# 12V_Buck.net
KiCad netlist of a schematic drawn in Altium Designer
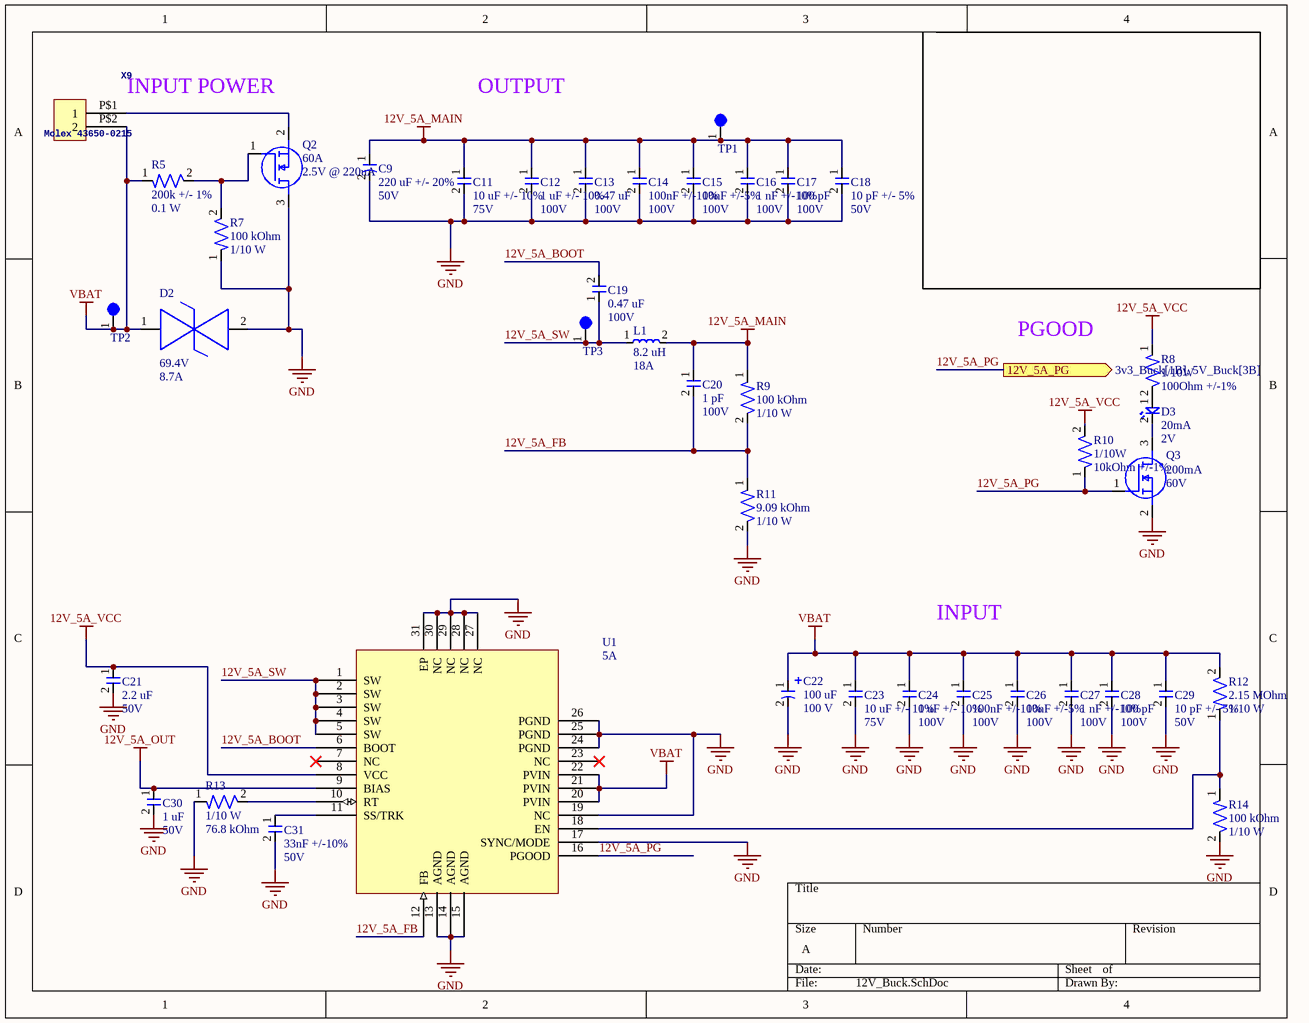
[diagram p0: 12V_Buck.SchDoc]

(export (version "E")
  (design (tool "Eeschema 10.0.6"))
  (components
    (comp (ref "C9")
      (value "50TZV220M10X10.5")
      (footprint "ELEC-220U-0003")
      (description "220 µF 50 V Aluminum Electrolytic Capacitors Radial, Can - SMD 2000 Hrs @ 105°C")
      (fields (field (name "CAPACITANCE") "220 uF +/- 20%") (field (name "VOLTAGE RATING") "50V"))
      (libsource (lib "MasterLib") (part "ELEC-220U-0003"))
    )
    (comp (ref "C11")
      (value "C3225X7R1N106K250AC")
      (footprint "CAP-1210")
      (description "10 µF ±10% 75V Ceramic Capacitor X7R 1210 (3225 Metric)")
      (fields (field (name "CAPACITANCE") "10 uF +/- 10%") (field (name "VOLTAGE RATING") "75V"))
      (libsource (lib "MasterLib") (part "CAP-10U-0004"))
    )
    (comp (ref "C12")
      (value "CL31B105KCHNNNE")
      (footprint "CAP-1206 - duplicate")
      (description "1 µF ±10% 100V Ceramic Capacitor X7R 1206 (3216 Metric)")
      (fields (field (name "CAPACITANCE") "1 uF +/- 10%") (field (name "VOLTAGE") "100V"))
      (libsource (lib "MasterLib") (part "CAP-1U-0001"))
    )
    (comp (ref "C13")
      (value "KAM21KR72A474KL")
      (footprint "CAP-0805")
      (description "0.47 µF ±10% 100V Ceramic Capacitor X7R 0805 (2012 Metric)")
      (fields
        (field (name "TOLERANCE") "+/- 10%")
        (field (name "CAPACITANCE") "0.47 uF")
        (field (name "VOLTAGE") "100V")
      )
      (libsource (lib "MasterLib") (part "CAP-0.47U-0001"))
    )
    (comp (ref "C14")
      (value "CC0603KRX7R0BB104")
      (footprint "CAP-0603")
      (description "CAP CER 0.1UF 100V X7R 0603")
      (fields
        (field (name "MANUFACTURER") "YAGEO")
        (field (name "CAPACITANCE") "100nF +/-10%")
        (field (name "VOLTAGE RATING") "100V")
      )
      (libsource (lib "MasterLib") (part "CAP-100N-0001"))
    )
    (comp (ref "C15")
      (value "C1608C0G2A103J080AC")
      (footprint "CAP-0603")
      (description "CAP CER 10000PF 100V C0G 0603")
      (fields
        (field (name "MANUFACTURER") "TDK Corporation")
        (field (name "CAPACITANCE") "10nF +/-5%")
        (field (name "VOLTAGE RATING") "100V")
      )
      (libsource (lib "MasterLib") (part "CAP-10N-0002"))
    )
    (comp (ref "C16")
      (value "C0603Y102K1RAC7867")
      (footprint "CAP-0603")
      (description "1000 pF ±10% 100V Ceramic Capacitor X7R 0603 (1608 Metric)")
      (fields (field (name "CAPACITANCE") "1 nF +/-10%") (field (name "VOLTAGE") "100V"))
      (libsource (lib "MasterLib") (part "CAP-1N-0001"))
    )
    (comp (ref "C17")
      (value "0603N101J101CT")
      (footprint "CAP-0603")
      (description "100 pF ±5% 100V Ceramic Capacitor C0G, NP0 0603 (1608 Metric)")
      (fields
        (field (name "TOLERANCE") "+/-5%")
        (field (name "CAPACITANCE") "100 pF")
        (field (name "VOLTAGE") "100V")
      )
      (libsource (lib "MasterLib") (part "CAP-100P-0002"))
    )
    (comp (ref "C18")
      (value "0603N100J500CT")
      (footprint "CAP-0603")
      (description "10 pF ±5% 50V Ceramic Capacitor C0G, NP0 0603 (1608 Metric)")
      (fields
        (field (name "MANUFACTURER") "Walshin Technology Corporation")
        (field (name "CAPACITANCE") "10 pF +/- 5%")
        (field (name "VOLTAGE RATING") "50V")
      )
      (libsource (lib "MasterLib") (part "CAP-10P-0001"))
    )
    (comp (ref "C19")
      (value "KAM21KR72A474KL")
      (footprint "CAP-0805")
      (description "0.47 µF ±10% 100V Ceramic Capacitor X7R 0805 (2012 Metric)")
      (fields
        (field (name "TOLERANCE") "+/- 10%")
        (field (name "CAPACITANCE") "0.47 uF")
        (field (name "VOLTAGE") "100V")
      )
      (libsource (lib "MasterLib") (part "CAP-0.47U-0001"))
    )
    (comp (ref "C20")
      (value "885012006087")
      (footprint "CAP-0603")
      (description "1 pF ±0.25pF 100V Ceramic Capacitor C0G, NP0 0603 (1608 Metric)")
      (fields
        (field (name "TOLERANCE") "+/- 0.25 pF")
        (field (name "CAPACITANCE") "1 pF")
        (field (name "VOLTAGE") "100V")
      )
      (libsource (lib "MasterLib") (part "CAP-1P-0001"))
    )
    (comp (ref "C21")
      (value "UMK107BBJ225KA-T")
      (footprint "CAP-0603")
      (description "2.2 µF ±10% 50V Ceramic Capacitor X5R 0603 (1608 Metric)")
      (fields (field (name "CAPACITANCE") "2.2 uF") (field (name "OLTAGE") "50V"))
      (libsource (lib "MasterLib") (part "CAP-2.2U-0001"))
    )
    (comp (ref "C22")
      (value "100SEV100M12.5X16")
      (footprint "ELEC-100U-0001")
      (description "100 µF 100 V Aluminum Electrolytic Capacitors Radial, Can - SMD 2000 Hrs @ 85°C")
      (fields
        (field (name "MANUFACTURER") "Rubycon")
        (field (name "TOLERANCE") "+/- 20%")
        (field (name "CAPACITANCE") "100 uF")
        (field (name "VOLTAGE") "100 V")
      )
      (libsource (lib "MasterLib") (part "ELEC-100U-0001"))
    )
    (comp (ref "C23")
      (value "C3225X7R1N106K250AC")
      (footprint "CAP-1210")
      (description "10 µF ±10% 75V Ceramic Capacitor X7R 1210 (3225 Metric)")
      (fields (field (name "CAPACITANCE") "10 uF +/- 10%") (field (name "VOLTAGE RATING") "75V"))
      (libsource (lib "MasterLib") (part "CAP-10U-0004"))
    )
    (comp (ref "C24")
      (value "CL31B105KCHNNNE")
      (footprint "CAP-1206 - duplicate")
      (description "1 µF ±10% 100V Ceramic Capacitor X7R 1206 (3216 Metric)")
      (fields (field (name "CAPACITANCE") "1 uF +/- 10%") (field (name "VOLTAGE") "100V"))
      (libsource (lib "MasterLib") (part "CAP-1U-0001"))
    )
    (comp (ref "C25")
      (value "CC0603KRX7R0BB104")
      (footprint "CAP-0603")
      (description "CAP CER 0.1UF 100V X7R 0603")
      (fields
        (field (name "MANUFACTURER") "YAGEO")
        (field (name "CAPACITANCE") "100nF +/-10%")
        (field (name "VOLTAGE RATING") "100V")
      )
      (libsource (lib "MasterLib") (part "CAP-100N-0001"))
    )
    (comp (ref "C26")
      (value "C1608C0G2A103J080AC")
      (footprint "CAP-0603")
      (description "CAP CER 10000PF 100V C0G 0603")
      (fields
        (field (name "MANUFACTURER") "TDK Corporation")
        (field (name "CAPACITANCE") "10nF +/-5%")
        (field (name "VOLTAGE RATING") "100V")
      )
      (libsource (lib "MasterLib") (part "CAP-10N-0002"))
    )
    (comp (ref "C27")
      (value "C0603Y102K1RAC7867")
      (footprint "CAP-0603")
      (description "1000 pF ±10% 100V Ceramic Capacitor X7R 0603 (1608 Metric)")
      (fields (field (name "CAPACITANCE") "1 nF +/-10%") (field (name "VOLTAGE") "100V"))
      (libsource (lib "MasterLib") (part "CAP-1N-0001"))
    )
    (comp (ref "C28")
      (value "0603N101J101CT")
      (footprint "CAP-0603")
      (description "100 pF ±5% 100V Ceramic Capacitor C0G, NP0 0603 (1608 Metric)")
      (fields
        (field (name "TOLERANCE") "+/-5%")
        (field (name "CAPACITANCE") "100 pF")
        (field (name "VOLTAGE") "100V")
      )
      (libsource (lib "MasterLib") (part "CAP-100P-0002"))
    )
    (comp (ref "C29")
      (value "0603N100J500CT")
      (footprint "CAP-0603")
      (description "10 pF ±5% 50V Ceramic Capacitor C0G, NP0 0603 (1608 Metric)")
      (fields
        (field (name "MANUFACTURER") "Walshin Technology Corporation")
        (field (name "CAPACITANCE") "10 pF +/- 5%")
        (field (name "VOLTAGE RATING") "50V")
      )
      (libsource (lib "MasterLib") (part "CAP-10P-0001"))
    )
    (comp (ref "C30")
      (value "UMK107AB7105KA-T")
      (footprint "CAP-0603")
      (description "1 µF ±10% 50V Ceramic Capacitor X7R 0603 (1608 Metric)")
      (fields (field (name "CAPACITANCE") "1 uF") (field (name "VOLTAGE") "50V"))
      (libsource (lib "MasterLib") (part "CAP-1U-0002"))
    )
    (comp (ref "C31")
      (value "CC0603KRX7R9BB333")
      (footprint "CAP-0603")
      (description "0.033 µF ±10% 50V Ceramic Capacitor X7R 0603 (1608 Metric)")
      (fields
        (field (name "MANUFACTURER") "YAGEO")
        (field (name "CAPACITANCE") "33nF +/-10%")
        (field (name "VOLTAGE RATING") "50V")
      )
      (libsource (lib "MasterLib") (part "CAP-33N-0001"))
    )
    (comp (ref "D2")
      (value "SMBJE43CAH")
      (footprint "DO-214AA (SMBJ)")
      (description "69.4V Clamp 8.7A Ipp Tvs Diode Surface Mount DO-214AA (SMBJ)")
      (fields (field (name "VCLAMP") "69.4V") (field (name "PEAK PULSER CURRENT") "8.7A"))
      (libsource (lib "MasterLib") (part "DIO-69.4V-0001"))
    )
    (comp (ref "D3")
      (value "150060AS75000")
      (footprint "LED-0603")
      (description "CAP CER 0.1UF 100V X7R 0603")
      (fields
        (field (name "MANUFACTURER") "Wurth Electronik")
        (field (name "CURRENT RATING") "20mA")
        (field (name "VF") "2V")
      )
      (libsource (lib "MasterLib") (part "LED_Amber_0001"))
    )
    (comp (ref "L1")
      (value "IHLP6767GZER8R2M01")
      (footprint "PWRIND-8.2U-0002")
      (description "8.2 µH Shielded Molded Inductor 18 A 10.66mOhm Max Nonstandard")
      (fields
        (field (name "TOLERANCE") "+/-20%")
        (field (name "INDUCTANCE") "8.2 uH")
        (field (name "DCI") "18A")
      )
      (libsource (lib "MasterLib") (part "PWRIND-8.2U-0002"))
    )
    (comp (ref "Q2")
      (value "TPH7R006PL,L1Q")
      (footprint "NMOS-8PowerVDFN")
      (description "N-Channel 60 V 60A (Tc) 81W (Tc) Surface Mount 8-SOP Advance (5x5)")
      (fields (field (name "DRAIN CURRENT") "60A") (field (name "VGS") "2.5V @ 220uA"))
      (libsource (lib "MasterLib") (part "NMOS-60A-0001"))
    )
    (comp (ref "Q3")
      (value "T2N7002AK,LM")
      (footprint "NMOS-SOT23-3")
      (description "MOSFET N-CH 60V 200MA SOT23")
      (fields
        (field (name "MANUFACTURER") "Toshiba")
        (field (name "ID-CONTINUOUS") "200mA")
        (field (name "VDS-MAX") "60V")
      )
      (libsource (lib "MasterLib") (part "NMOS-200MA-0001"))
    )
    (comp (ref "R5")
      (value "ERJ-3EKF2003V")
      (footprint "RES-0603")
      (description "200 kOhms ±1% 0.1W, 1/10W Chip Resistor 0603 (1608 Metric) Automotive AEC-Q200 Thick Film")
      (fields
        (field (name "MANUFACTURER") "Panasonic Electronic Components")
        (field (name "RESISTANCE") "200k +/- 1%")
        (field (name "POWER RATING") "0.1 W")
      )
      (libsource (lib "MasterLib") (part "RES-200K-0001"))
    )
    (comp (ref "R7")
      (value "RC0603FR-07100KL")
      (footprint "RES-0603")
      (description "100 kOhms ±1% 0.1W, 1/10W Chip Resistor 0603 (1608 Metric) Moisture Resistant Thick Film")
      (fields
        (field (name "TOLERANCE") "+/- 1%")
        (field (name "RESISTANCE") "100 kOhm")
        (field (name "POWER") "1/10 W")
      )
      (libsource (lib "MasterLib") (part "RES-100K-0003"))
    )
    (comp (ref "R8")
      (value "AC0603FR-10100RL")
      (footprint "RES-0603")
      (description "100 Ohms ±1% 0.1W, 1/10W Chip Resistor 0603 (1608 Metric) Automotive AEC-Q200 Thick Film")
      (fields
        (field (name "MANUFACTURER") "YAGEO")
        (field (name "POWER RATING") "1/10W")
        (field (name "RESISTANCE") "100Ohm +/-1%")
      )
      (libsource (lib "MasterLib") (part "RES-100-0002"))
    )
    (comp (ref "R9")
      (value "RC0603FR-07100KL")
      (footprint "RES-0603")
      (description "100 kOhms ±1% 0.1W, 1/10W Chip Resistor 0603 (1608 Metric) Moisture Resistant Thick Film")
      (fields
        (field (name "TOLERANCE") "+/- 1%")
        (field (name "RESISTANCE") "100 kOhm")
        (field (name "POWER") "1/10 W")
      )
      (libsource (lib "MasterLib") (part "RES-100K-0003"))
    )
    (comp (ref "R10")
      (value "RC0603FR-0710KP")
      (footprint "RES-0603")
      (description "RES SMD 10K OHM 1% 1/10W 0603")
      (fields
        (field (name "MANUFACTURER") "YAGEO")
        (field (name "POWER RATING") "1/10W")
        (field (name "RESISTANCE") "10kOhm +/-1%")
      )
      (libsource (lib "MasterLib") (part "RES-10K-0002"))
    )
    (comp (ref "R11")
      (value "RC0603FR-079K09L")
      (footprint "RES-0603")
      (description "9.09 kOhms ±1% 0.1W, 1/10W Chip Resistor 0603 (1608 Metric) Moisture Resistant Thick Film")
      (fields
        (field (name "TOLERANCE") "+/-1%")
        (field (name "RESISTANCE") "9.09 kOhm")
        (field (name "POWER") "1/10 W")
      )
      (libsource (lib "MasterLib") (part "RES-9.09K-0001"))
    )
    (comp (ref "R12")
      (value "RC0603FR-072M15L")
      (footprint "RES-0603")
      (description "2.15 MOhms ±1% 0.1W, 1/10W Chip Resistor 0603 (1608 Metric) Moisture Resistant Thick Film")
      (fields
        (field (name "TOLERANCE") "+/-1%")
        (field (name "RESISTANCE") "2.15 MOhm")
        (field (name "POWER") "1/10 W")
      )
      (libsource (lib "MasterLib") (part "RES-2.15M-0001"))
    )
    (comp (ref "R13")
      (value "RC0603FR-0776K8L")
      (footprint "RES-0603")
      (description "76.8 kOhms ±1% 0.1W, 1/10W Chip Resistor 0603 (1608 Metric) Moisture Resistant Thick Film")
      (fields
        (field (name "MANUFACTURER") "Yageo")
        (field (name "TOLERANCE") "+/- 1%")
        (field (name "POWER") "1/10 W")
        (field (name "RESISTANCE") "76.8 kOhm")
      )
      (libsource (lib "MasterLib") (part "RES-76.8K-0001"))
    )
    (comp (ref "R14")
      (value "RC0603FR-07100KL")
      (footprint "RES-0603")
      (description "100 kOhms ±1% 0.1W, 1/10W Chip Resistor 0603 (1608 Metric) Moisture Resistant Thick Film")
      (fields
        (field (name "TOLERANCE") "+/- 1%")
        (field (name "RESISTANCE") "100 kOhm")
        (field (name "POWER") "1/10 W")
      )
      (libsource (lib "MasterLib") (part "RES-100K-0003"))
    )
    (comp (ref "TP1")
      (value "5003")
      (footprint "TEST-POINT-0001")
      (description "Oranange PC Test Point, Miniature Phoisphor Bronze Silver Plating Through Hole Mounting Type")
      (libsource (lib "MasterLib") (part "TEST-POINT-0001"))
    )
    (comp (ref "TP2")
      (value "5003")
      (footprint "TEST-POINT-0001")
      (description "Oranange PC Test Point, Miniature Phoisphor Bronze Silver Plating Through Hole Mounting Type")
      (libsource (lib "MasterLib") (part "TEST-POINT-0001"))
    )
    (comp (ref "TP3")
      (value "5003")
      (footprint "TEST-POINT-0001")
      (description "Oranange PC Test Point, Miniature Phoisphor Bronze Silver Plating Through Hole Mounting Type")
      (libsource (lib "MasterLib") (part "TEST-POINT-0001"))
    )
    (comp (ref "U1")
      (value "LM76005RNPR")
      (footprint "IC-30-WQFN(6x4)")
      (description "Buck Switching Regulator IC Positive Adjustable 1V 1 Output 5A 30-WFQFN Exposed Pad")
      (fields (field (name "MANUFACTURER") "Texas Instruments") (field (name "CURRENT") "5A"))
      (libsource (lib "MasterLib") (part "IC-BUCK-0006"))
    )
    (comp (ref "X9")
      (value "Molex 43650-0215")
      (footprint "43650-0215")
      (libsource (lib "Molex Microfit") (part "Micro-Fit Molex 2 Pin Vertical"))
    )
  )
  (nets
    (net (code "1") (name "/12V_5A_BOOT") (class "Default")
      (node (ref "C19") (pin "2") (pinfunction "2_2") (pintype "passive"))
      (node (ref "U1") (pin "6") (pinfunction "BOOT_6") (pintype "power_in"))
    )
    (net (code "2") (name "/12V_5A_FB") (class "Default")
      (node (ref "C20") (pin "2") (pinfunction "2_2") (pintype "passive"))
      (node (ref "R11") (pin "1") (pinfunction "1_1") (pintype "passive"))
      (node (ref "R9") (pin "2") (pinfunction "2_2") (pintype "passive"))
      (node (ref "U1") (pin "12") (pinfunction "FB_12") (pintype "input"))
    )
    (net (code "3") (name "/12V_5A_PG") (class "Default")
      (node (ref "Q3") (pin "1") (pinfunction "G_1") (pintype "passive"))
      (node (ref "R10") (pin "1") (pinfunction "1_1") (pintype "passive"))
      (node (ref "U1") (pin "16") (pinfunction "PGOOD_16") (pintype "power_in"))
    )
    (net (code "4") (name "/12V_5A_SW") (class "Default")
      (node (ref "C19") (pin "1") (pinfunction "1_1") (pintype "passive"))
      (node (ref "L1") (pin "1") (pinfunction "1_1") (pintype "passive"))
      (node (ref "TP3") (pin "1") (pinfunction "0_1") (pintype "passive"))
      (node (ref "U1") (pin "1") (pinfunction "SW_1") (pintype "power_in"))
      (node (ref "U1") (pin "2") (pinfunction "SW_2") (pintype "power_in"))
      (node (ref "U1") (pin "3") (pinfunction "SW_3") (pintype "power_in"))
      (node (ref "U1") (pin "4") (pinfunction "SW_4") (pintype "power_in"))
      (node (ref "U1") (pin "5") (pinfunction "SW_5") (pintype "power_in"))
    )
    (net (code "5") (name "12V_5A_MAIN") (class "Default")
      (node (ref "C11") (pin "1") (pinfunction "1_1") (pintype "passive"))
      (node (ref "C12") (pin "1") (pinfunction "1_1") (pintype "passive"))
      (node (ref "C13") (pin "1") (pinfunction "1_1") (pintype "passive"))
      (node (ref "C14") (pin "1") (pinfunction "1_1") (pintype "passive"))
      (node (ref "C15") (pin "1") (pinfunction "1_1") (pintype "passive"))
      (node (ref "C16") (pin "1") (pinfunction "1_1") (pintype "passive"))
      (node (ref "C17") (pin "1") (pinfunction "1_1") (pintype "passive"))
      (node (ref "C18") (pin "1") (pinfunction "1_1") (pintype "passive"))
      (node (ref "C20") (pin "1") (pinfunction "1_1") (pintype "passive"))
      (node (ref "C9") (pin "1") (pinfunction "1_1") (pintype "passive"))
      (node (ref "L1") (pin "2") (pinfunction "2_2") (pintype "passive"))
      (node (ref "R9") (pin "1") (pinfunction "1_1") (pintype "passive"))
      (node (ref "TP1") (pin "1") (pinfunction "0_1") (pintype "passive"))
    )
    (net (code "6") (name "12V_5A_OUT") (class "Default")
      (node (ref "C30") (pin "1") (pinfunction "1_1") (pintype "passive"))
      (node (ref "U1") (pin "9") (pinfunction "BIAS_9") (pintype "power_in"))
    )
    (net (code "7") (name "12V_5A_VCC") (class "Default")
      (node (ref "C21") (pin "1") (pinfunction "1_1") (pintype "passive"))
      (node (ref "R10") (pin "2") (pinfunction "2_2") (pintype "passive"))
      (node (ref "R8") (pin "1") (pinfunction "1_1") (pintype "passive"))
      (node (ref "U1") (pin "8") (pinfunction "VCC_8") (pintype "power_in"))
    )
    (net (code "8") (name "GND") (class "Default")
      (node (ref "C11") (pin "2") (pinfunction "2_2") (pintype "passive"))
      (node (ref "C12") (pin "2") (pinfunction "2_2") (pintype "passive"))
      (node (ref "C13") (pin "2") (pinfunction "2_2") (pintype "passive"))
      (node (ref "C14") (pin "2") (pinfunction "2_2") (pintype "passive"))
      (node (ref "C15") (pin "2") (pinfunction "2_2") (pintype "passive"))
      (node (ref "C16") (pin "2") (pinfunction "2_2") (pintype "passive"))
      (node (ref "C17") (pin "2") (pinfunction "2_2") (pintype "passive"))
      (node (ref "C18") (pin "2") (pinfunction "2_2") (pintype "passive"))
      (node (ref "C21") (pin "2") (pinfunction "2_2") (pintype "passive"))
      (node (ref "C22") (pin "2") (pinfunction "2_2") (pintype "passive"))
      (node (ref "C23") (pin "2") (pinfunction "2_2") (pintype "passive"))
      (node (ref "C24") (pin "2") (pinfunction "2_2") (pintype "passive"))
      (node (ref "C25") (pin "2") (pinfunction "2_2") (pintype "passive"))
      (node (ref "C26") (pin "2") (pinfunction "2_2") (pintype "passive"))
      (node (ref "C27") (pin "2") (pinfunction "2_2") (pintype "passive"))
      (node (ref "C28") (pin "2") (pinfunction "2_2") (pintype "passive"))
      (node (ref "C29") (pin "2") (pinfunction "2_2") (pintype "passive"))
      (node (ref "C30") (pin "2") (pinfunction "2_2") (pintype "passive"))
      (node (ref "C31") (pin "2") (pinfunction "2_2") (pintype "passive"))
      (node (ref "C9") (pin "2") (pinfunction "2_2") (pintype "passive"))
      (node (ref "D2") (pin "2") (pintype "passive"))
      (node (ref "Q2") (pin "3") (pinfunction "D_3") (pintype "passive"))
      (node (ref "Q3") (pin "2") (pinfunction "S_2") (pintype "passive"))
      (node (ref "R11") (pin "2") (pinfunction "2_2") (pintype "passive"))
      (node (ref "R13") (pin "1") (pinfunction "1_1") (pintype "passive"))
      (node (ref "R14") (pin "2") (pinfunction "2_2") (pintype "passive"))
      (node (ref "R7") (pin "1") (pinfunction "1_1") (pintype "passive"))
      (node (ref "U1") (pin "13") (pinfunction "AGND_13") (pintype "power_in"))
      (node (ref "U1") (pin "14") (pinfunction "AGND_14") (pintype "power_in"))
      (node (ref "U1") (pin "15") (pinfunction "AGND_15") (pintype "power_in"))
      (node (ref "U1") (pin "17") (pinfunction "SYNC/MODE_17") (pintype "power_in"))
      (node (ref "U1") (pin "19") (pinfunction "NC_19") (pintype "power_in"))
      (node (ref "U1") (pin "24") (pinfunction "PGND_24") (pintype "power_in"))
      (node (ref "U1") (pin "25") (pinfunction "PGND_25") (pintype "power_in"))
      (node (ref "U1") (pin "26") (pinfunction "PGND_26") (pintype "power_in"))
      (node (ref "U1") (pin "27") (pinfunction "NC_27") (pintype "power_in"))
      (node (ref "U1") (pin "28") (pinfunction "NC_28") (pintype "power_in"))
      (node (ref "U1") (pin "29") (pinfunction "NC_29") (pintype "power_in"))
      (node (ref "U1") (pin "30") (pinfunction "NC_30") (pintype "power_in"))
      (node (ref "U1") (pin "31") (pinfunction "EP_31") (pintype "power_in"))
    )
    (net (code "9") (name "Net-(D3-Pad1)") (class "Default")
      (node (ref "D3") (pin "1") (pinfunction "1_1") (pintype "passive"))
      (node (ref "R8") (pin "2") (pinfunction "2_2") (pintype "passive"))
    )
    (net (code "10") (name "Net-(Q2-G)") (class "Default")
      (node (ref "Q2") (pin "1") (pinfunction "G_1") (pintype "passive"))
      (node (ref "R5") (pin "2") (pinfunction "2_2") (pintype "passive"))
      (node (ref "R7") (pin "2") (pinfunction "2_2") (pintype "passive"))
    )
    (net (code "11") (name "Net-(Q2-S)") (class "Default")
      (node (ref "Q2") (pin "2") (pinfunction "S_2") (pintype "passive"))
      (node (ref "X9") (pin "P$1") (pinfunction "1_P$1") (pintype "passive"))
    )
    (net (code "12") (name "Net-(Q3-D)") (class "Default")
      (node (ref "D3") (pin "2") (pinfunction "2_2") (pintype "passive"))
      (node (ref "Q3") (pin "3") (pinfunction "D_3") (pintype "passive"))
    )
    (net (code "13") (name "Net-(U1-EN)") (class "Default")
      (node (ref "R12") (pin "1") (pinfunction "1_1") (pintype "passive"))
      (node (ref "R14") (pin "1") (pinfunction "1_1") (pintype "passive"))
      (node (ref "U1") (pin "18") (pinfunction "EN_18") (pintype "power_in"))
    )
    (net (code "14") (name "Net-(U1-RT)") (class "Default")
      (node (ref "R13") (pin "2") (pinfunction "2_2") (pintype "passive"))
      (node (ref "U1") (pin "10") (pinfunction "RT_10") (pintype "bidirectional"))
    )
    (net (code "15") (name "Net-(U1-SS{slash}TRK)") (class "Default")
      (node (ref "C31") (pin "1") (pinfunction "1_1") (pintype "passive"))
      (node (ref "U1") (pin "11") (pinfunction "SS/TRK_11") (pintype "passive"))
    )
    (net (code "16") (name "VBAT") (class "Default")
      (node (ref "C22") (pin "1") (pinfunction "1_1") (pintype "passive"))
      (node (ref "C23") (pin "1") (pinfunction "1_1") (pintype "passive"))
      (node (ref "C24") (pin "1") (pinfunction "1_1") (pintype "passive"))
      (node (ref "C25") (pin "1") (pinfunction "1_1") (pintype "passive"))
      (node (ref "C26") (pin "1") (pinfunction "1_1") (pintype "passive"))
      (node (ref "C27") (pin "1") (pinfunction "1_1") (pintype "passive"))
      (node (ref "C28") (pin "1") (pinfunction "1_1") (pintype "passive"))
      (node (ref "C29") (pin "1") (pinfunction "1_1") (pintype "passive"))
      (node (ref "D2") (pin "1") (pintype "passive"))
      (node (ref "R12") (pin "2") (pinfunction "2_2") (pintype "passive"))
      (node (ref "R5") (pin "1") (pinfunction "1_1") (pintype "passive"))
      (node (ref "TP2") (pin "1") (pinfunction "0_1") (pintype "passive"))
      (node (ref "U1") (pin "20") (pinfunction "PVIN_20") (pintype "power_in"))
      (node (ref "U1") (pin "21") (pinfunction "PVIN_21") (pintype "power_in"))
      (node (ref "U1") (pin "22") (pinfunction "PVIN_22") (pintype "power_in"))
      (node (ref "X9") (pin "P$2") (pinfunction "2_P$2") (pintype "passive"))
    )
    (net (code "17") (name "unconnected-(U1-NC-Pad7)") (class "Default")
      (node (ref "U1") (pin "7") (pinfunction "NC_7") (pintype "power_in+no_connect"))
    )
    (net (code "18") (name "unconnected-(U1-NC-Pad23)") (class "Default")
      (node (ref "U1") (pin "23") (pinfunction "NC_23") (pintype "tri_state+no_connect"))
    )
  )
)
